# Debug_Interface.net
KiCad netlist of a schematic drawn in Altium Designer
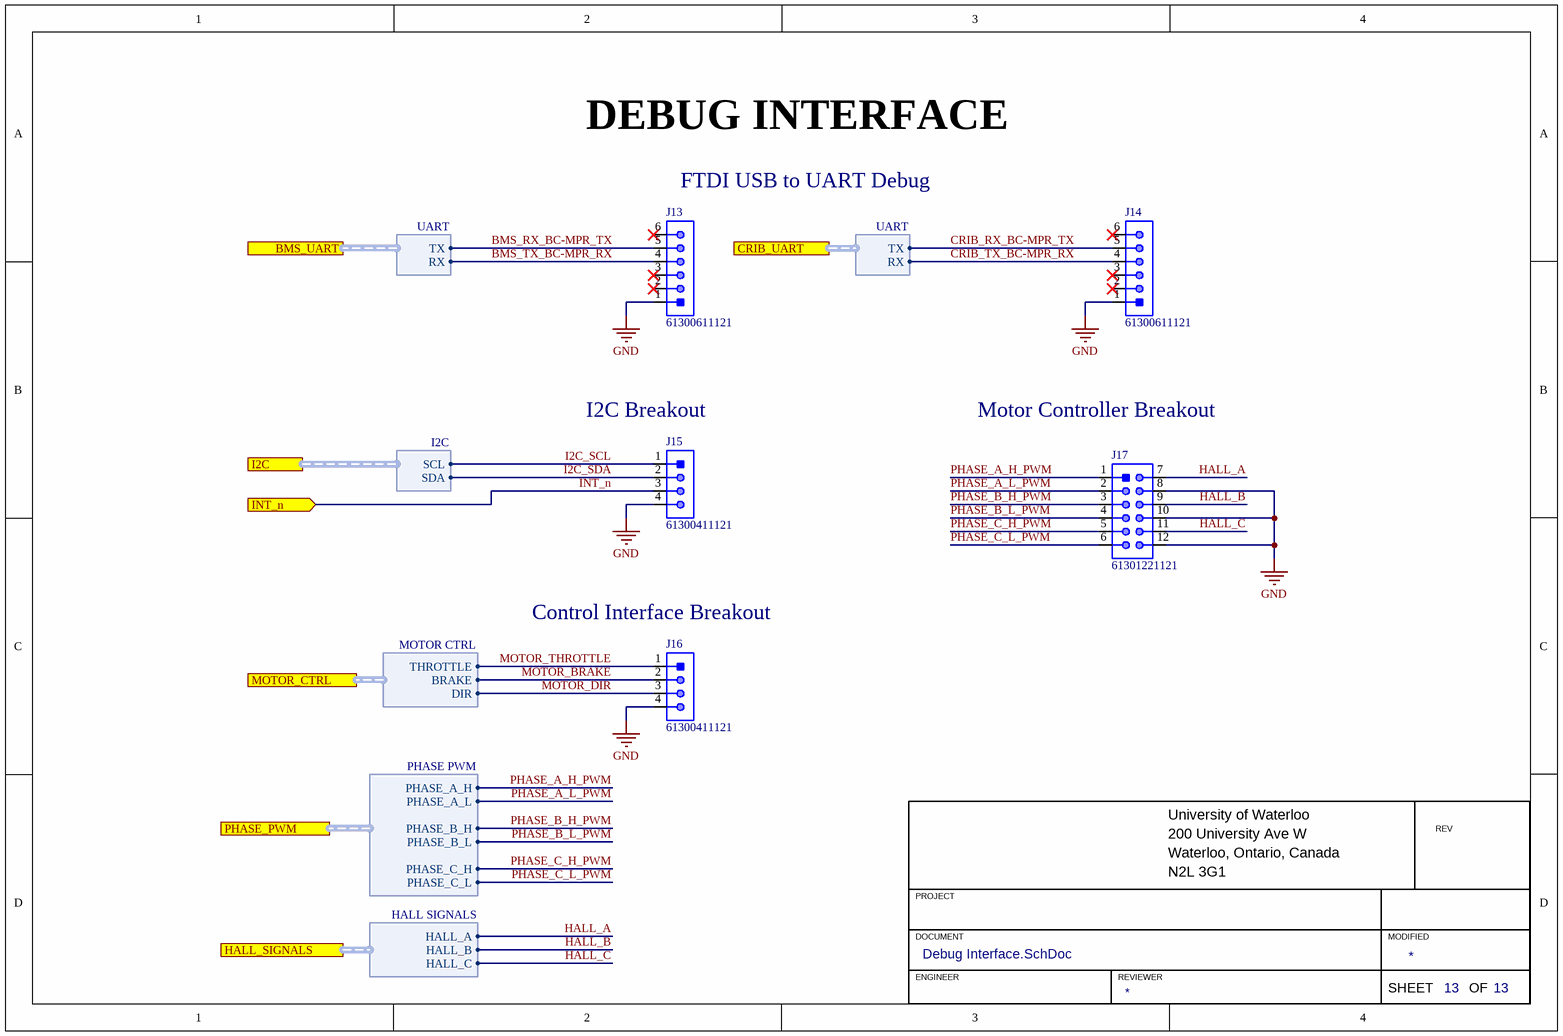
[diagram p0: Debug Interface.SchDoc]

(export (version "E")
  (design (tool "Eeschema 10.0.6"))
  (components
    (comp (ref "J13")
      (value "HEADER 6x1")
      (footprint "HDR1X6")
      (description "CONN HEADER VERT 6POS 2.54MM")
      (fields (field (name "MANUFACTURER PART NUMBER 1") "61300611121"))
      (libsource (lib "Personal_Schematic_Library_2022") (part "HEADER 6x1"))
    )
    (comp (ref "J14")
      (value "HEADER 6x1")
      (footprint "HDR1X6")
      (description "CONN HEADER VERT 6POS 2.54MM")
      (fields (field (name "MANUFACTURER PART NUMBER 1") "61300611121"))
      (libsource (lib "Personal_Schematic_Library_2022") (part "HEADER 6x1"))
    )
    (comp (ref "J15")
      (value "HEADER 4x1")
      (footprint "HDR1X4")
      (description "CONN HEADER VERT 4POS 2.54MM")
      (fields (field (name "MANUFACTURER PART NUMBER 1") "61300411121"))
      (libsource (lib "Personal_Schematic_Library_2022") (part "HEADER 4x1"))
    )
    (comp (ref "J16")
      (value "HEADER 4x1")
      (footprint "HDR1X4")
      (description "CONN HEADER VERT 4POS 2.54MM")
      (fields (field (name "MANUFACTURER PART NUMBER 1") "61300411121"))
      (libsource (lib "Personal_Schematic_Library_2022") (part "HEADER 4x1"))
    )
    (comp (ref "J17")
      (value "HEADER 6x2")
      (footprint "HDR2X6")
      (description "CONN HEADER VERT 12POS 2.54MM")
      (fields (field (name "MANUFACTURER PART NUMBER 1") "61301221121"))
      (libsource (lib "Personal_Schematic_Library_2022") (part "HEADER 6x2"))
    )
  )
  (nets
    (net (code "9") (name "/BMS_RX_BC-MPR_TX") (class "Default")
      (node (ref "J13") (pin "5") (pinfunction "5_5") (pintype "passive"))
    )
    (net (code "10") (name "/BMS_TX_BC-MPR_RX") (class "Default")
      (node (ref "J13") (pin "4") (pinfunction "4_4") (pintype "passive"))
    )
    (net (code "11") (name "/CRIB_RX_BC-MPR_TX") (class "Default")
      (node (ref "J14") (pin "5") (pinfunction "5_5") (pintype "passive"))
    )
    (net (code "12") (name "/CRIB_TX_BC-MPR_RX") (class "Default")
      (node (ref "J14") (pin "4") (pinfunction "4_4") (pintype "passive"))
    )
    (net (code "13") (name "/HALL_A") (class "Default")
      (node (ref "J17") (pin "7") (pinfunction "7_7") (pintype "passive"))
    )
    (net (code "14") (name "/HALL_B") (class "Default")
      (node (ref "J17") (pin "9") (pinfunction "9_9") (pintype "passive"))
    )
    (net (code "15") (name "/HALL_C") (class "Default")
      (node (ref "J17") (pin "11") (pinfunction "11_11") (pintype "passive"))
    )
    (net (code "16") (name "/I2C_SCL") (class "Default")
      (node (ref "J15") (pin "1") (pinfunction "1_1") (pintype "passive"))
    )
    (net (code "17") (name "/I2C_SDA") (class "Default")
      (node (ref "J15") (pin "2") (pinfunction "2_2") (pintype "passive"))
    )
    (net (code "18") (name "/INT_n") (class "Default")
      (node (ref "J15") (pin "3") (pinfunction "3_3") (pintype "passive"))
    )
    (net (code "19") (name "/MOTOR_BRAKE") (class "Default")
      (node (ref "J16") (pin "2") (pinfunction "2_2") (pintype "passive"))
    )
    (net (code "20") (name "/MOTOR_DIR") (class "Default")
      (node (ref "J16") (pin "3") (pinfunction "3_3") (pintype "passive"))
    )
    (net (code "21") (name "/MOTOR_THROTTLE") (class "Default")
      (node (ref "J16") (pin "1") (pinfunction "1_1") (pintype "passive"))
    )
    (net (code "22") (name "/PHASE_A_H_PWM") (class "Default")
      (node (ref "J17") (pin "1") (pinfunction "1_1") (pintype "passive"))
    )
    (net (code "23") (name "/PHASE_A_L_PWM") (class "Default")
      (node (ref "J17") (pin "2") (pinfunction "2_2") (pintype "passive"))
    )
    (net (code "24") (name "/PHASE_B_H_PWM") (class "Default")
      (node (ref "J17") (pin "3") (pinfunction "3_3") (pintype "passive"))
    )
    (net (code "25") (name "/PHASE_B_L_PWM") (class "Default")
      (node (ref "J17") (pin "4") (pinfunction "4_4") (pintype "passive"))
    )
    (net (code "26") (name "/PHASE_C_H_PWM") (class "Default")
      (node (ref "J17") (pin "5") (pinfunction "5_5") (pintype "passive"))
    )
    (net (code "27") (name "/PHASE_C_L_PWM") (class "Default")
      (node (ref "J17") (pin "6") (pinfunction "6_6") (pintype "passive"))
    )
    (net (code "33") (name "GND") (class "Default")
      (node (ref "J13") (pin "1") (pinfunction "1_1") (pintype "passive"))
      (node (ref "J14") (pin "1") (pinfunction "1_1") (pintype "passive"))
      (node (ref "J15") (pin "4") (pinfunction "4_4") (pintype "passive"))
      (node (ref "J16") (pin "4") (pinfunction "4_4") (pintype "passive"))
      (node (ref "J17") (pin "10") (pinfunction "10_10") (pintype "passive"))
      (node (ref "J17") (pin "12") (pinfunction "12_12") (pintype "passive"))
      (node (ref "J17") (pin "8") (pinfunction "8_8") (pintype "passive"))
    )
    (net (code "34") (name "unconnected-(J13-Pad2)") (class "Default")
      (node (ref "J13") (pin "2") (pinfunction "2_2") (pintype "passive+no_connect"))
    )
    (net (code "35") (name "unconnected-(J13-Pad3)") (class "Default")
      (node (ref "J13") (pin "3") (pinfunction "3_3") (pintype "passive+no_connect"))
    )
    (net (code "36") (name "unconnected-(J13-Pad6)") (class "Default")
      (node (ref "J13") (pin "6") (pinfunction "6_6") (pintype "passive+no_connect"))
    )
    (net (code "37") (name "unconnected-(J14-Pad2)") (class "Default")
      (node (ref "J14") (pin "2") (pinfunction "2_2") (pintype "passive+no_connect"))
    )
    (net (code "38") (name "unconnected-(J14-Pad3)") (class "Default")
      (node (ref "J14") (pin "3") (pinfunction "3_3") (pintype "passive+no_connect"))
    )
    (net (code "39") (name "unconnected-(J14-Pad6)") (class "Default")
      (node (ref "J14") (pin "6") (pinfunction "6_6") (pintype "passive+no_connect"))
    )
  )
)
